# LED_Matrix.net
KiCad netlist of a schematic drawn in Altium Designer
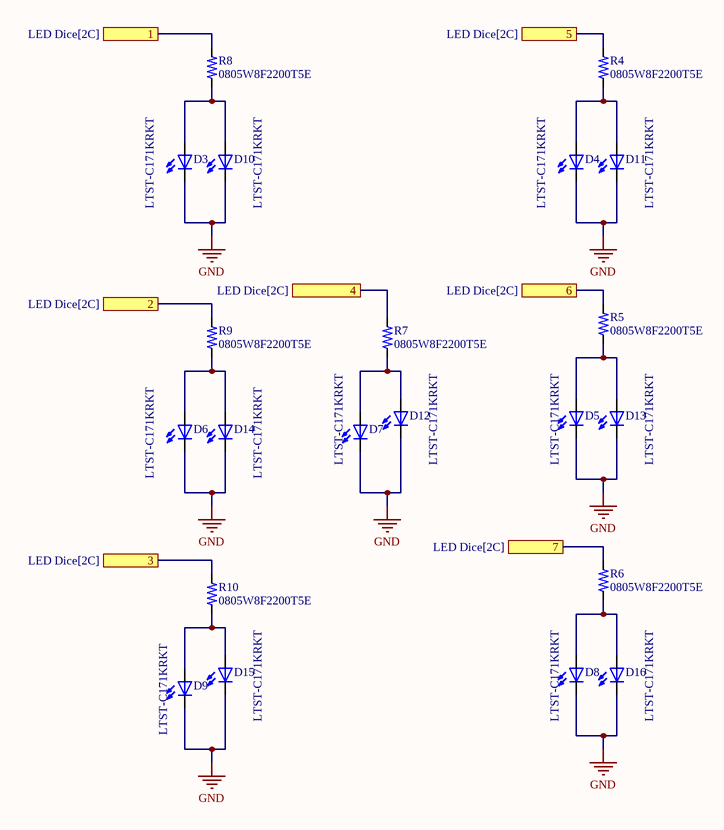
[diagram p0: LED Matrix.SchDoc]

(export (version "E")
  (design (tool "Eeschema 10.0.6"))
  (components
    (comp (ref "D3")
      (value "LTST-C171KRKT")
      (footprint "DIOC200X125X110")
      (description "Red LED  0805 _2012 Indication 631nm - Discrete 2V 0805 _2012 Metric_")
      (fields (field (name "MF") "Lite-On Inc."))
      (libsource (lib "LTST-C171KRKT") (part "LTST-C171KRKT"))
    )
    (comp (ref "D4")
      (value "LTST-C171KRKT")
      (footprint "DIOC200X125X110")
      (description "Red LED  0805 _2012 Indication 631nm - Discrete 2V 0805 _2012 Metric_")
      (fields (field (name "MF") "Lite-On Inc."))
      (libsource (lib "LTST-C171KRKT") (part "LTST-C171KRKT"))
    )
    (comp (ref "D5")
      (value "LTST-C171KRKT")
      (footprint "DIOC200X125X110")
      (description "Red LED  0805 _2012 Indication 631nm - Discrete 2V 0805 _2012 Metric_")
      (fields (field (name "MF") "Lite-On Inc."))
      (libsource (lib "LTST-C171KRKT") (part "LTST-C171KRKT"))
    )
    (comp (ref "D6")
      (value "LTST-C171KRKT")
      (footprint "DIOC200X125X110")
      (description "Red LED  0805 _2012 Indication 631nm - Discrete 2V 0805 _2012 Metric_")
      (fields (field (name "MF") "Lite-On Inc."))
      (libsource (lib "LTST-C171KRKT") (part "LTST-C171KRKT"))
    )
    (comp (ref "D7")
      (value "LTST-C171KRKT")
      (footprint "DIOC200X125X110")
      (description "Red LED  0805 _2012 Indication 631nm - Discrete 2V 0805 _2012 Metric_")
      (fields (field (name "MF") "Lite-On Inc."))
      (libsource (lib "LTST-C171KRKT") (part "LTST-C171KRKT"))
    )
    (comp (ref "D8")
      (value "LTST-C171KRKT")
      (footprint "DIOC200X125X110")
      (description "Red LED  0805 _2012 Indication 631nm - Discrete 2V 0805 _2012 Metric_")
      (fields (field (name "MF") "Lite-On Inc."))
      (libsource (lib "LTST-C171KRKT") (part "LTST-C171KRKT"))
    )
    (comp (ref "D9")
      (value "LTST-C171KRKT")
      (footprint "DIOC200X125X110")
      (description "Red LED  0805 _2012 Indication 631nm - Discrete 2V 0805 _2012 Metric_")
      (fields (field (name "MF") "Lite-On Inc."))
      (libsource (lib "LTST-C171KRKT") (part "LTST-C171KRKT"))
    )
    (comp (ref "D10")
      (value "LTST-C171KRKT")
      (footprint "DIOC200X125X110")
      (description "Red LED  0805 _2012 Indication 631nm - Discrete 2V 0805 _2012 Metric_")
      (fields (field (name "MF") "Lite-On Inc."))
      (libsource (lib "LTST-C171KRKT") (part "LTST-C171KRKT"))
    )
    (comp (ref "D11")
      (value "LTST-C171KRKT")
      (footprint "DIOC200X125X110")
      (description "Red LED  0805 _2012 Indication 631nm - Discrete 2V 0805 _2012 Metric_")
      (fields (field (name "MF") "Lite-On Inc."))
      (libsource (lib "LTST-C171KRKT") (part "LTST-C171KRKT"))
    )
    (comp (ref "D12")
      (value "LTST-C171KRKT")
      (footprint "DIOC200X125X110")
      (description "Red LED  0805 _2012 Indication 631nm - Discrete 2V 0805 _2012 Metric_")
      (fields (field (name "MF") "Lite-On Inc."))
      (libsource (lib "LTST-C171KRKT") (part "LTST-C171KRKT"))
    )
    (comp (ref "D13")
      (value "LTST-C171KRKT")
      (footprint "DIOC200X125X110")
      (description "Red LED  0805 _2012 Indication 631nm - Discrete 2V 0805 _2012 Metric_")
      (fields (field (name "MF") "Lite-On Inc."))
      (libsource (lib "LTST-C171KRKT") (part "LTST-C171KRKT"))
    )
    (comp (ref "D14")
      (value "LTST-C171KRKT")
      (footprint "DIOC200X125X110")
      (description "Red LED  0805 _2012 Indication 631nm - Discrete 2V 0805 _2012 Metric_")
      (fields (field (name "MF") "Lite-On Inc."))
      (libsource (lib "LTST-C171KRKT") (part "LTST-C171KRKT"))
    )
    (comp (ref "D15")
      (value "LTST-C171KRKT")
      (footprint "DIOC200X125X110")
      (description "Red LED  0805 _2012 Indication 631nm - Discrete 2V 0805 _2012 Metric_")
      (fields (field (name "MF") "Lite-On Inc."))
      (libsource (lib "LTST-C171KRKT") (part "LTST-C171KRKT"))
    )
    (comp (ref "D16")
      (value "LTST-C171KRKT")
      (footprint "DIOC200X125X110")
      (description "Red LED  0805 _2012 Indication 631nm - Discrete 2V 0805 _2012 Metric_")
      (fields (field (name "MF") "Lite-On Inc."))
      (libsource (lib "LTST-C171KRKT") (part "LTST-C171KRKT"))
    )
    (comp (ref "R4")
      (value "0805W8F2200T5E")
      (footprint "RESC2012X65N")
      (description "220Ω 0805 125mW Thick Film Resistors 150V ±100ppm/℃ ±1%  Chip Resistor - Surface Mount ROHS")
      (libsource (lib "CRT0805-BW-1002ELF") (part "0805W8F2200T5E"))
    )
    (comp (ref "R5")
      (value "0805W8F2200T5E")
      (footprint "RESC2012X65N")
      (description "220Ω 0805 125mW Thick Film Resistors 150V ±100ppm/℃ ±1%  Chip Resistor - Surface Mount ROHS")
      (libsource (lib "CRT0805-BW-1002ELF") (part "0805W8F2200T5E"))
    )
    (comp (ref "R6")
      (value "0805W8F2200T5E")
      (footprint "RESC2012X65N")
      (description "220Ω 0805 125mW Thick Film Resistors 150V ±100ppm/℃ ±1%  Chip Resistor - Surface Mount ROHS")
      (libsource (lib "CRT0805-BW-1002ELF") (part "0805W8F2200T5E"))
    )
    (comp (ref "R7")
      (value "0805W8F2200T5E")
      (footprint "RESC2012X65N")
      (description "220Ω 0805 125mW Thick Film Resistors 150V ±100ppm/℃ ±1%  Chip Resistor - Surface Mount ROHS")
      (libsource (lib "CRT0805-BW-1002ELF") (part "0805W8F2200T5E"))
    )
    (comp (ref "R8")
      (value "0805W8F2200T5E")
      (footprint "RESC2012X65N")
      (description "220Ω 0805 125mW Thick Film Resistors 150V ±100ppm/℃ ±1%  Chip Resistor - Surface Mount ROHS")
      (libsource (lib "CRT0805-BW-1002ELF") (part "0805W8F2200T5E"))
    )
    (comp (ref "R9")
      (value "0805W8F2200T5E")
      (footprint "RESC2012X65N")
      (description "220Ω 0805 125mW Thick Film Resistors 150V ±100ppm/℃ ±1%  Chip Resistor - Surface Mount ROHS")
      (libsource (lib "CRT0805-BW-1002ELF") (part "0805W8F2200T5E"))
    )
    (comp (ref "R10")
      (value "0805W8F2200T5E")
      (footprint "RESC2012X65N")
      (description "220Ω 0805 125mW Thick Film Resistors 150V ±100ppm/℃ ±1%  Chip Resistor - Surface Mount ROHS")
      (libsource (lib "CRT0805-BW-1002ELF") (part "0805W8F2200T5E"))
    )
  )
  (nets
    (net (code "1") (name "/1") (class "Default")
      (node (ref "R8") (pin "2") (pinfunction "2_2") (pintype "passive"))
    )
    (net (code "2") (name "/2") (class "Default")
      (node (ref "R9") (pin "2") (pinfunction "2_2") (pintype "passive"))
    )
    (net (code "3") (name "/3") (class "Default")
      (node (ref "R10") (pin "2") (pinfunction "2_2") (pintype "passive"))
    )
    (net (code "4") (name "/4") (class "Default")
      (node (ref "R7") (pin "2") (pinfunction "2_2") (pintype "passive"))
    )
    (net (code "5") (name "/5") (class "Default")
      (node (ref "R4") (pin "2") (pinfunction "2_2") (pintype "passive"))
    )
    (net (code "6") (name "/6") (class "Default")
      (node (ref "R5") (pin "2") (pinfunction "2_2") (pintype "passive"))
    )
    (net (code "7") (name "/7") (class "Default")
      (node (ref "R6") (pin "2") (pinfunction "2_2") (pintype "passive"))
    )
    (net (code "8") (name "GND") (class "Default")
      (node (ref "D10") (pin "NEG") (pinfunction "NEG_NEG") (pintype "passive"))
      (node (ref "D11") (pin "NEG") (pinfunction "NEG_NEG") (pintype "passive"))
      (node (ref "D12") (pin "NEG") (pinfunction "NEG_NEG") (pintype "passive"))
      (node (ref "D13") (pin "NEG") (pinfunction "NEG_NEG") (pintype "passive"))
      (node (ref "D14") (pin "NEG") (pinfunction "NEG_NEG") (pintype "passive"))
      (node (ref "D15") (pin "NEG") (pinfunction "NEG_NEG") (pintype "passive"))
      (node (ref "D16") (pin "NEG") (pinfunction "NEG_NEG") (pintype "passive"))
      (node (ref "D3") (pin "NEG") (pinfunction "NEG_NEG") (pintype "passive"))
      (node (ref "D4") (pin "NEG") (pinfunction "NEG_NEG") (pintype "passive"))
      (node (ref "D5") (pin "NEG") (pinfunction "NEG_NEG") (pintype "passive"))
      (node (ref "D6") (pin "NEG") (pinfunction "NEG_NEG") (pintype "passive"))
      (node (ref "D7") (pin "NEG") (pinfunction "NEG_NEG") (pintype "passive"))
      (node (ref "D8") (pin "NEG") (pinfunction "NEG_NEG") (pintype "passive"))
      (node (ref "D9") (pin "NEG") (pinfunction "NEG_NEG") (pintype "passive"))
    )
    (net (code "9") (name "Net-(D10-PadPOS)") (class "Default")
      (node (ref "D10") (pin "POS") (pinfunction "POS_POS") (pintype "passive"))
      (node (ref "D3") (pin "POS") (pinfunction "POS_POS") (pintype "passive"))
      (node (ref "R8") (pin "1") (pinfunction "1_1") (pintype "passive"))
    )
    (net (code "10") (name "Net-(D11-PadPOS)") (class "Default")
      (node (ref "D11") (pin "POS") (pinfunction "POS_POS") (pintype "passive"))
      (node (ref "D4") (pin "POS") (pinfunction "POS_POS") (pintype "passive"))
      (node (ref "R4") (pin "1") (pinfunction "1_1") (pintype "passive"))
    )
    (net (code "11") (name "Net-(D12-PadPOS)") (class "Default")
      (node (ref "D12") (pin "POS") (pinfunction "POS_POS") (pintype "passive"))
      (node (ref "D7") (pin "POS") (pinfunction "POS_POS") (pintype "passive"))
      (node (ref "R7") (pin "1") (pinfunction "1_1") (pintype "passive"))
    )
    (net (code "12") (name "Net-(D13-PadPOS)") (class "Default")
      (node (ref "D13") (pin "POS") (pinfunction "POS_POS") (pintype "passive"))
      (node (ref "D5") (pin "POS") (pinfunction "POS_POS") (pintype "passive"))
      (node (ref "R5") (pin "1") (pinfunction "1_1") (pintype "passive"))
    )
    (net (code "13") (name "Net-(D14-PadPOS)") (class "Default")
      (node (ref "D14") (pin "POS") (pinfunction "POS_POS") (pintype "passive"))
      (node (ref "D6") (pin "POS") (pinfunction "POS_POS") (pintype "passive"))
      (node (ref "R9") (pin "1") (pinfunction "1_1") (pintype "passive"))
    )
    (net (code "14") (name "Net-(D15-PadPOS)") (class "Default")
      (node (ref "D15") (pin "POS") (pinfunction "POS_POS") (pintype "passive"))
      (node (ref "D9") (pin "POS") (pinfunction "POS_POS") (pintype "passive"))
      (node (ref "R10") (pin "1") (pinfunction "1_1") (pintype "passive"))
    )
    (net (code "15") (name "Net-(D16-PadPOS)") (class "Default")
      (node (ref "D16") (pin "POS") (pinfunction "POS_POS") (pintype "passive"))
      (node (ref "D8") (pin "POS") (pinfunction "POS_POS") (pintype "passive"))
      (node (ref "R6") (pin "1") (pinfunction "1_1") (pintype "passive"))
    )
  )
)
